# Engine_Room_ADUM_Arduino.net
KiCad netlist of a schematic drawn in EAGLE
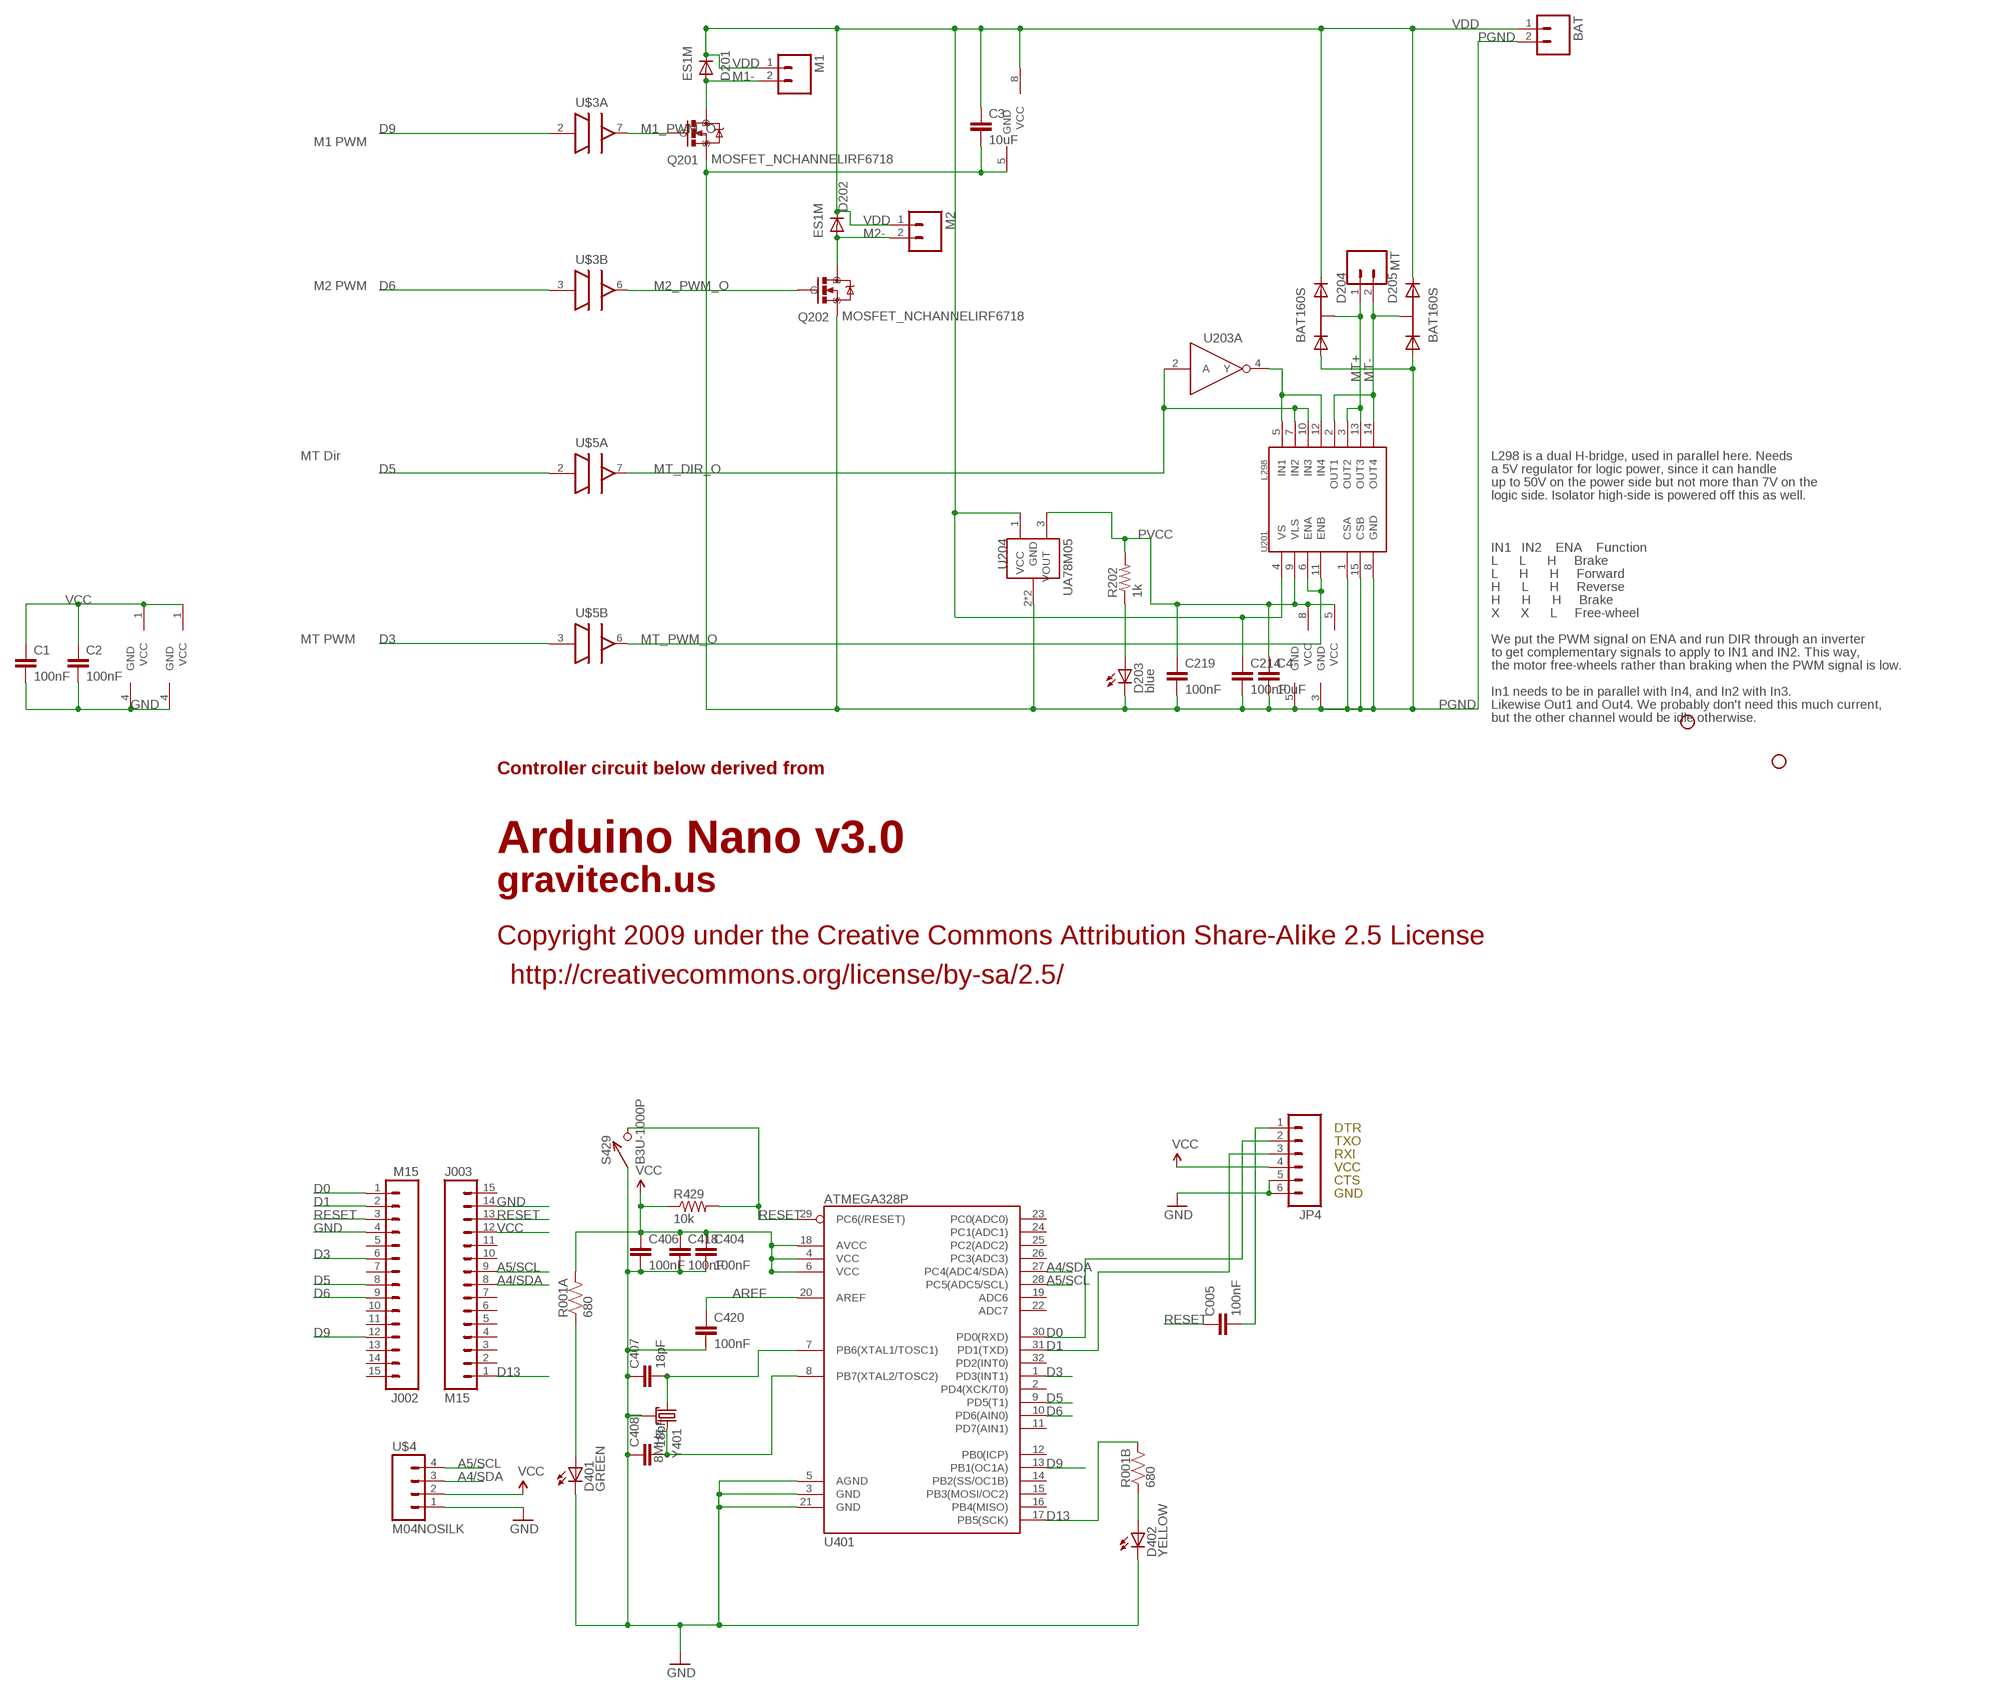
[diagram p0: schematic, sheet 1]

(export (version "E")
  (design (tool "Eeschema 10.0.6"))
  (components
    (comp (ref "BAT")
      (value "M02PTH4")
      (footprint "eagle-import:1X02_XTRA_BIG")
      (libsource (lib "eagle-import") (part "M02PTH4"))
    )
    (comp (ref "C1")
      (value "100nF")
      (footprint "eagle-import:0402-CAP")
      (libsource (lib "eagle-import") (part "CAP0402-CAP"))
    )
    (comp (ref "C2")
      (value "100nF")
      (footprint "eagle-import:0402-CAP")
      (libsource (lib "eagle-import") (part "CAP0402-CAP"))
    )
    (comp (ref "C3")
      (value "10uF")
      (footprint "eagle-import:1206")
      (libsource (lib "eagle-import") (part "SparkFun-Passives_CAP1206"))
    )
    (comp (ref "C4")
      (value "10uF")
      (footprint "eagle-import:1206")
      (libsource (lib "eagle-import") (part "SparkFun-Passives_CAP1206"))
    )
    (comp (ref "C005")
      (value "100nF")
      (footprint "eagle-import:0402-CAP")
      (libsource (lib "eagle-import") (part "CAP0402-CAP"))
    )
    (comp (ref "C214")
      (value "100nF")
      (footprint "eagle-import:1206")
      (libsource (lib "eagle-import") (part "SparkFun-Passives_CAP1206"))
    )
    (comp (ref "C219")
      (value "100nF")
      (footprint "eagle-import:0402-CAP")
      (libsource (lib "eagle-import") (part "CAP0402-CAP"))
    )
    (comp (ref "C404")
      (value "100nF")
      (footprint "eagle-import:0402-CAP")
      (libsource (lib "eagle-import") (part "CAP0402-CAP"))
    )
    (comp (ref "C406")
      (value "100nF")
      (footprint "eagle-import:0402-CAP")
      (libsource (lib "eagle-import") (part "CAP0402-CAP"))
    )
    (comp (ref "C407")
      (value "18pF")
      (footprint "eagle-import:0402-CAP")
      (libsource (lib "eagle-import") (part "CAP0402-CAP"))
    )
    (comp (ref "C408")
      (value "18pF")
      (footprint "eagle-import:0402-CAP")
      (libsource (lib "eagle-import") (part "CAP0402-CAP"))
    )
    (comp (ref "C418")
      (value "100nF")
      (footprint "eagle-import:0402-CAP")
      (libsource (lib "eagle-import") (part "CAP0402-CAP"))
    )
    (comp (ref "C420")
      (value "100nF")
      (footprint "eagle-import:0402-CAP")
      (libsource (lib "eagle-import") (part "CAP0402-CAP"))
    )
    (comp (ref "D201")
      (value "ES1M")
      (footprint "eagle-import:DO-214AC")
      (libsource (lib "eagle-import") (part "DIODE-DO-214AC"))
    )
    (comp (ref "D202")
      (value "ES1M")
      (footprint "eagle-import:DO-214AC")
      (libsource (lib "eagle-import") (part "DIODE-DO-214AC"))
    )
    (comp (ref "D203")
      (value "blue")
      (footprint "eagle-import:LED-0603")
      (libsource (lib "eagle-import") (part "LED0603"))
    )
    (comp (ref "D204")
      (value "BAT160S")
      (footprint "eagle-import:SOT-223")
      (libsource (lib "eagle-import") (part "BAT160S"))
    )
    (comp (ref "D205")
      (value "BAT160S")
      (footprint "eagle-import:SOT-223")
      (libsource (lib "eagle-import") (part "BAT160S"))
    )
    (comp (ref "D401")
      (value "GREEN")
      (footprint "eagle-import:LED-0603")
      (libsource (lib "eagle-import") (part "SparkFun-LED_LED0603"))
    )
    (comp (ref "D402")
      (value "YELLOW")
      (footprint "eagle-import:LED-0603")
      (libsource (lib "eagle-import") (part "SparkFun-LED_LED0603"))
    )
    (comp (ref "J002")
      (value "M15")
      (footprint "eagle-import:1X15")
      (libsource (lib "eagle-import") (part "M15"))
    )
    (comp (ref "J003")
      (value "M15")
      (footprint "eagle-import:1X15")
      (libsource (lib "eagle-import") (part "M15"))
    )
    (comp (ref "JP1")
      (value "STAND-OFF")
      (footprint "eagle-import:STAND-OFF")
      (libsource (lib "eagle-import") (part "STAND-OFF"))
    )
    (comp (ref "JP2")
      (value "STAND-OFF")
      (footprint "eagle-import:STAND-OFF")
      (libsource (lib "eagle-import") (part "STAND-OFF"))
    )
    (comp (ref "JP4")
      (value "M06SIP")
      (footprint "eagle-import:1X06")
      (libsource (lib "eagle-import") (part "M06SIP"))
    )
    (comp (ref "M1")
      (value "M02PTH4")
      (footprint "eagle-import:1X02_XTRA_BIG")
      (libsource (lib "eagle-import") (part "M02PTH4"))
    )
    (comp (ref "M2")
      (value "M02PTH4")
      (footprint "eagle-import:1X02_XTRA_BIG")
      (libsource (lib "eagle-import") (part "M02PTH4"))
    )
    (comp (ref "MT")
      (value "M02PTH")
      (footprint "eagle-import:1X02")
      (libsource (lib "eagle-import") (part "M02PTH"))
    )
    (comp (ref "Q201")
      (value "MOSFET_NCHANNELIRF6718")
      (footprint "eagle-import:DIRECTFET_L6")
      (libsource (lib "eagle-import") (part "MOSFET_NCHANNELIRF6718"))
    )
    (comp (ref "Q202")
      (value "MOSFET_NCHANNELIRF6718")
      (footprint "eagle-import:DIRECTFET_L6")
      (libsource (lib "eagle-import") (part "MOSFET_NCHANNELIRF6718"))
    )
    (comp (ref "R001")
      (value "680")
      (footprint "eagle-import:CRA02")
      (fields (field (name "DIGIKEY") "CRA4S8680CT-ND"))
      (libsource (lib "eagle-import") (part "RP2EXB24V"))
    )
    (comp (ref "R202")
      (value "1k")
      (footprint "eagle-import:0402-RES")
      (libsource (lib "eagle-import") (part "RESISTOR0402-RES"))
    )
    (comp (ref "R429")
      (value "10k")
      (footprint "eagle-import:0402-RES")
      (libsource (lib "eagle-import") (part "SparkFun-Passives_RESISTOR0402-RES"))
    )
    (comp (ref "S429")
      (value "B3U-1000P")
      (footprint "eagle-import:B3U-1000P")
      (libsource (lib "eagle-import") (part "B3U-1000P"))
    )
    (comp (ref "U$3")
      (value "ADUM3221")
      (footprint "eagle-import:SO8N")
      (libsource (lib "eagle-import") (part "ADUM3221"))
    )
    (comp (ref "U$4")
      (value "M04NOSILK")
      (footprint "eagle-import:M04SIP")
      (libsource (lib "eagle-import") (part "M04NOSILK"))
    )
    (comp (ref "U$5")
      (value "ADUM3221")
      (footprint "eagle-import:SO8N")
      (libsource (lib "eagle-import") (part "ADUM3221"))
    )
    (comp (ref "U201")
      (value "L298")
      (footprint "eagle-import:MULTIWATT15")
      (libsource (lib "eagle-import") (part "L298"))
    )
    (comp (ref "U203")
      (value "MC74VHC1G04")
      (footprint "eagle-import:SOT-23-5")
      (libsource (lib "eagle-import") (part "MC74VHC1G04"))
    )
    (comp (ref "U204")
      (value "UA78M05")
      (footprint "eagle-import:SOT-223")
      (libsource (lib "eagle-import") (part "UA78M05"))
    )
    (comp (ref "U401")
      (value "ATMEGA328P")
      (footprint "eagle-import:TQFP32-08")
      (libsource (lib "eagle-import") (part "ATMEGA168"))
    )
    (comp (ref "Y401")
      (value "8MHz")
      (footprint "eagle-import:CRYSTAL_SMD_2MM_2_5MM")
      (libsource (lib "eagle-import") (part "CX2520"))
    )
  )
  (nets
    (net (code "1") (name "/A4{slash}SDA") (class "Default")
      (node (ref "J003") (pin "8") (pinfunction "8_8") (pintype "passive"))
      (node (ref "U$4") (pin "3") (pinfunction "3_3") (pintype "passive"))
      (node (ref "U401") (pin "27") (pinfunction "PC4(ADC4/SDA)_27") (pintype "bidirectional"))
    )
    (net (code "2") (name "/A5{slash}SCL") (class "Default")
      (node (ref "J003") (pin "9") (pinfunction "9_9") (pintype "passive"))
      (node (ref "U$4") (pin "4") (pinfunction "4_4") (pintype "passive"))
      (node (ref "U401") (pin "28") (pinfunction "PC5(ADC5/SCL)_28") (pintype "bidirectional"))
    )
    (net (code "3") (name "/AREF") (class "Default")
      (node (ref "C420") (pin "1") (pinfunction "1_1") (pintype "passive"))
      (node (ref "U401") (pin "20") (pinfunction "AREF_20") (pintype "bidirectional"))
    )
    (net (code "4") (name "/D0") (class "Default")
      (node (ref "J002") (pin "1") (pinfunction "1_1") (pintype "passive"))
      (node (ref "JP4") (pin "2") (pinfunction "2_2") (pintype "passive"))
      (node (ref "U401") (pin "30") (pinfunction "PD0(RXD)_30") (pintype "bidirectional"))
    )
    (net (code "5") (name "/D1") (class "Default")
      (node (ref "J002") (pin "2") (pinfunction "2_2") (pintype "passive"))
      (node (ref "JP4") (pin "3") (pinfunction "3_3") (pintype "passive"))
      (node (ref "U401") (pin "31") (pinfunction "PD1(TXD)_31") (pintype "bidirectional"))
    )
    (net (code "6") (name "/D3") (class "Default")
      (node (ref "J002") (pin "6") (pinfunction "6_6") (pintype "passive"))
      (node (ref "U$5") (pin "3") (pinfunction "IN_3") (pintype "input"))
      (node (ref "U401") (pin "1") (pinfunction "PD3(INT1)_1") (pintype "bidirectional"))
    )
    (net (code "7") (name "/D5") (class "Default")
      (node (ref "J002") (pin "8") (pinfunction "8_8") (pintype "passive"))
      (node (ref "U$5") (pin "2") (pinfunction "IN_2") (pintype "input"))
      (node (ref "U401") (pin "9") (pinfunction "PD5(T1)_9") (pintype "bidirectional"))
    )
    (net (code "8") (name "/D6") (class "Default")
      (node (ref "J002") (pin "9") (pinfunction "9_9") (pintype "passive"))
      (node (ref "U$3") (pin "3") (pinfunction "IN_3") (pintype "input"))
      (node (ref "U401") (pin "10") (pinfunction "PD6(AIN0)_10") (pintype "bidirectional"))
    )
    (net (code "9") (name "/D9") (class "Default")
      (node (ref "J002") (pin "12") (pinfunction "12_12") (pintype "passive"))
      (node (ref "U$3") (pin "2") (pinfunction "IN_2") (pintype "input"))
      (node (ref "U401") (pin "13") (pinfunction "PB1(OC1A)_13") (pintype "bidirectional"))
    )
    (net (code "10") (name "/D13") (class "Default")
      (node (ref "J003") (pin "1") (pinfunction "1_1") (pintype "passive"))
      (node (ref "R001") (pin "3") (pinfunction "2_3") (pintype "passive"))
      (node (ref "U401") (pin "17") (pinfunction "PB5(SCK)_17") (pintype "bidirectional"))
    )
    (net (code "11") (name "/M1-") (class "Default")
      (node (ref "D201") (pin "A") (pinfunction "A_A") (pintype "passive"))
      (node (ref "M1") (pin "2") (pinfunction "2_2") (pintype "passive"))
      (node (ref "Q201") (pin "D1") (pinfunction "D_D1") (pintype "passive"))
      (node (ref "Q201") (pin "D2") (pinfunction "D_D2") (pintype "passive"))
    )
    (net (code "12") (name "/M1_PWM_O") (class "Default")
      (node (ref "Q201") (pin "G") (pinfunction "G_G") (pintype "passive"))
      (node (ref "U$3") (pin "7") (pinfunction "OUT_7") (pintype "bidirectional"))
    )
    (net (code "13") (name "/M2-") (class "Default")
      (node (ref "D202") (pin "A") (pinfunction "A_A") (pintype "passive"))
      (node (ref "M2") (pin "2") (pinfunction "2_2") (pintype "passive"))
      (node (ref "Q202") (pin "D1") (pinfunction "D_D1") (pintype "passive"))
      (node (ref "Q202") (pin "D2") (pinfunction "D_D2") (pintype "passive"))
    )
    (net (code "14") (name "/M2_PWM_O") (class "Default")
      (node (ref "Q202") (pin "G") (pinfunction "G_G") (pintype "passive"))
      (node (ref "U$3") (pin "6") (pinfunction "OUT_6") (pintype "bidirectional"))
    )
    (net (code "15") (name "/MT+") (class "Default")
      (node (ref "D204") (pin "4") (pinfunction "K1A2_4") (pintype "passive"))
      (node (ref "MT") (pin "1") (pinfunction "1_1") (pintype "passive"))
      (node (ref "U201") (pin "13") (pinfunction "OUT3_13") (pintype "bidirectional"))
      (node (ref "U201") (pin "3") (pinfunction "OUT2_3") (pintype "bidirectional"))
    )
    (net (code "16") (name "/MT-") (class "Default")
      (node (ref "D205") (pin "4") (pinfunction "K1A2_4") (pintype "passive"))
      (node (ref "MT") (pin "2") (pinfunction "2_2") (pintype "passive"))
      (node (ref "U201") (pin "14") (pinfunction "OUT4_14") (pintype "bidirectional"))
      (node (ref "U201") (pin "2") (pinfunction "OUT1_2") (pintype "bidirectional"))
    )
    (net (code "17") (name "/MT_DIR_O") (class "Default")
      (node (ref "U$5") (pin "7") (pinfunction "OUT_7") (pintype "bidirectional"))
      (node (ref "U201") (pin "10") (pinfunction "IN3_10") (pintype "bidirectional"))
      (node (ref "U201") (pin "7") (pinfunction "IN2_7") (pintype "bidirectional"))
      (node (ref "U203") (pin "2") (pinfunction "A_2") (pintype "input"))
    )
    (net (code "18") (name "/MT_PWM_O") (class "Default")
      (node (ref "U$5") (pin "6") (pinfunction "OUT_6") (pintype "bidirectional"))
      (node (ref "U201") (pin "11") (pinfunction "ENB_11") (pintype "bidirectional"))
      (node (ref "U201") (pin "6") (pinfunction "ENA_6") (pintype "bidirectional"))
    )
    (net (code "19") (name "/PGND") (class "Default")
      (node (ref "BAT") (pin "2") (pinfunction "2_2") (pintype "passive"))
      (node (ref "C214") (pin "2") (pinfunction "2_2") (pintype "passive"))
      (node (ref "C219") (pin "2") (pinfunction "2_2") (pintype "passive"))
      (node (ref "C3") (pin "2") (pinfunction "2_2") (pintype "passive"))
      (node (ref "C4") (pin "2") (pinfunction "2_2") (pintype "passive"))
      (node (ref "D203") (pin "C") (pinfunction "C_C") (pintype "passive"))
      (node (ref "D204") (pin "1") (pinfunction "A1_1") (pintype "passive"))
      (node (ref "D205") (pin "1") (pinfunction "A1_1") (pintype "passive"))
      (node (ref "Q201") (pin "S") (pinfunction "S_S") (pintype "passive"))
      (node (ref "Q202") (pin "S") (pinfunction "S_S") (pintype "passive"))
      (node (ref "U$3") (pin "5") (pinfunction "GND_5") (pintype "bidirectional"))
      (node (ref "U$5") (pin "5") (pinfunction "GND_5") (pintype "bidirectional"))
      (node (ref "U201") (pin "1") (pinfunction "CSA_1") (pintype "bidirectional"))
      (node (ref "U201") (pin "15") (pinfunction "CSB_15") (pintype "bidirectional"))
      (node (ref "U201") (pin "8") (pinfunction "GND_8") (pintype "bidirectional"))
      (node (ref "U203") (pin "3") (pinfunction "GND_3") (pintype "bidirectional"))
      (node (ref "U204") (pin "2") (pinfunction "GND_2") (pintype "bidirectional"))
      (node (ref "U204") (pin "4") (pinfunction "GND_4") (pintype "bidirectional"))
    )
    (net (code "20") (name "/PVCC") (class "Default")
      (node (ref "C219") (pin "1") (pinfunction "1_1") (pintype "passive"))
      (node (ref "C4") (pin "1") (pinfunction "1_1") (pintype "passive"))
      (node (ref "R202") (pin "2") (pinfunction "2_2") (pintype "passive"))
      (node (ref "U$5") (pin "8") (pinfunction "VCC_8") (pintype "bidirectional"))
      (node (ref "U201") (pin "9") (pinfunction "VLS_9") (pintype "bidirectional"))
      (node (ref "U203") (pin "5") (pinfunction "VCC_5") (pintype "bidirectional"))
      (node (ref "U204") (pin "3") (pinfunction "VOUT_3") (pintype "bidirectional"))
    )
    (net (code "21") (name "/RESET") (class "Default")
      (node (ref "C005") (pin "1") (pinfunction "1_1") (pintype "passive"))
      (node (ref "J002") (pin "3") (pinfunction "3_3") (pintype "passive"))
      (node (ref "J003") (pin "13") (pinfunction "13_13") (pintype "passive"))
      (node (ref "R429") (pin "2") (pinfunction "2_2") (pintype "passive"))
      (node (ref "S429") (pin "P$2") (pinfunction "2_P$2") (pintype "bidirectional"))
      (node (ref "U401") (pin "29") (pinfunction "PC6(/RESET)_29") (pintype "bidirectional"))
    )
    (net (code "22") (name "/VDD") (class "Default")
      (node (ref "BAT") (pin "1") (pinfunction "1_1") (pintype "passive"))
      (node (ref "C214") (pin "1") (pinfunction "1_1") (pintype "passive"))
      (node (ref "C3") (pin "1") (pinfunction "1_1") (pintype "passive"))
      (node (ref "D201") (pin "C") (pinfunction "C_C") (pintype "passive"))
      (node (ref "D202") (pin "C") (pinfunction "C_C") (pintype "passive"))
      (node (ref "D204") (pin "3") (pinfunction "K2_3") (pintype "passive"))
      (node (ref "D205") (pin "3") (pinfunction "K2_3") (pintype "passive"))
      (node (ref "M1") (pin "1") (pinfunction "1_1") (pintype "passive"))
      (node (ref "M2") (pin "1") (pinfunction "1_1") (pintype "passive"))
      (node (ref "U$3") (pin "8") (pinfunction "VCC_8") (pintype "bidirectional"))
      (node (ref "U201") (pin "4") (pinfunction "VS_4") (pintype "bidirectional"))
      (node (ref "U204") (pin "1") (pinfunction "VCC_1") (pintype "bidirectional"))
    )
    (net (code "23") (name "GND") (class "Default")
      (node (ref "C1") (pin "2") (pinfunction "2_2") (pintype "passive"))
      (node (ref "C2") (pin "2") (pinfunction "2_2") (pintype "passive"))
      (node (ref "C404") (pin "2") (pinfunction "2_2") (pintype "passive"))
      (node (ref "C406") (pin "2") (pinfunction "2_2") (pintype "passive"))
      (node (ref "C407") (pin "1") (pinfunction "1_1") (pintype "passive"))
      (node (ref "C408") (pin "1") (pinfunction "1_1") (pintype "passive"))
      (node (ref "C418") (pin "2") (pinfunction "2_2") (pintype "passive"))
      (node (ref "C420") (pin "2") (pinfunction "2_2") (pintype "passive"))
      (node (ref "D401") (pin "C") (pinfunction "C_C") (pintype "passive"))
      (node (ref "D402") (pin "C") (pinfunction "C_C") (pintype "passive"))
      (node (ref "J002") (pin "4") (pinfunction "4_4") (pintype "passive"))
      (node (ref "J003") (pin "14") (pinfunction "14_14") (pintype "passive"))
      (node (ref "JP4") (pin "5") (pinfunction "5_5") (pintype "passive"))
      (node (ref "JP4") (pin "6") (pinfunction "6_6") (pintype "passive"))
      (node (ref "S429") (pin "P$1") (pinfunction "1_P$1") (pintype "bidirectional"))
      (node (ref "U$3") (pin "4") (pinfunction "GND_4") (pintype "bidirectional"))
      (node (ref "U$4") (pin "1") (pinfunction "1_1") (pintype "passive"))
      (node (ref "U$5") (pin "4") (pinfunction "GND_4") (pintype "bidirectional"))
      (node (ref "U401") (pin "21") (pinfunction "GND_21") (pintype "bidirectional"))
      (node (ref "U401") (pin "3") (pinfunction "GND_3") (pintype "bidirectional"))
      (node (ref "U401") (pin "5") (pinfunction "AGND_5") (pintype "bidirectional"))
      (node (ref "Y401") (pin "2") (pinfunction "GND_2") (pintype "passive"))
      (node (ref "Y401") (pin "4") (pinfunction "GND_4") (pintype "passive"))
    )
    (net (code "24") (name "Net-(C005-Pad2)") (class "Default")
      (node (ref "C005") (pin "2") (pinfunction "2_2") (pintype "passive"))
      (node (ref "JP4") (pin "1") (pinfunction "1_1") (pintype "passive"))
    )
    (net (code "25") (name "Net-(D203-PadA)") (class "Default")
      (node (ref "D203") (pin "A") (pinfunction "A_A") (pintype "passive"))
      (node (ref "R202") (pin "1") (pinfunction "1_1") (pintype "passive"))
    )
    (net (code "26") (name "Net-(D401-PadA)") (class "Default")
      (node (ref "D401") (pin "A") (pinfunction "A_A") (pintype "passive"))
      (node (ref "R001") (pin "1") (pinfunction "1_1") (pintype "passive"))
    )
    (net (code "27") (name "Net-(R001B-1)") (class "Default")
      (node (ref "D402") (pin "A") (pinfunction "A_A") (pintype "passive"))
      (node (ref "R001") (pin "2") (pinfunction "1_2") (pintype "passive"))
    )
    (net (code "28") (name "Net-(U201-IN1)") (class "Default")
      (node (ref "U201") (pin "12") (pinfunction "IN4_12") (pintype "bidirectional"))
      (node (ref "U201") (pin "5") (pinfunction "IN1_5") (pintype "bidirectional"))
      (node (ref "U203") (pin "4") (pinfunction "Y_4") (pintype "output"))
    )
    (net (code "29") (name "Net-(U401-PB6(XTAL1{slash}TOSC1))") (class "Default")
      (node (ref "C407") (pin "2") (pinfunction "2_2") (pintype "passive"))
      (node (ref "U401") (pin "7") (pinfunction "PB6(XTAL1/TOSC1)_7") (pintype "bidirectional"))
      (node (ref "Y401") (pin "1") (pinfunction "1_1") (pintype "passive"))
    )
    (net (code "30") (name "Net-(U401-PB7(XTAL2{slash}TOSC2))") (class "Default")
      (node (ref "C408") (pin "2") (pinfunction "2_2") (pintype "passive"))
      (node (ref "U401") (pin "8") (pinfunction "PB7(XTAL2/TOSC2)_8") (pintype "bidirectional"))
      (node (ref "Y401") (pin "3") (pinfunction "2_3") (pintype "passive"))
    )
    (net (code "31") (name "VCC") (class "Default")
      (node (ref "C1") (pin "1") (pinfunction "1_1") (pintype "passive"))
      (node (ref "C2") (pin "1") (pinfunction "1_1") (pintype "passive"))
      (node (ref "C404") (pin "1") (pinfunction "1_1") (pintype "passive"))
      (node (ref "C406") (pin "1") (pinfunction "1_1") (pintype "passive"))
      (node (ref "C418") (pin "1") (pinfunction "1_1") (pintype "passive"))
      (node (ref "J003") (pin "12") (pinfunction "12_12") (pintype "passive"))
      (node (ref "JP4") (pin "4") (pinfunction "4_4") (pintype "passive"))
      (node (ref "R001") (pin "4") (pinfunction "2_4") (pintype "passive"))
      (node (ref "R429") (pin "1") (pinfunction "1_1") (pintype "passive"))
      (node (ref "U$3") (pin "1") (pinfunction "VCC_1") (pintype "bidirectional"))
      (node (ref "U$4") (pin "2") (pinfunction "2_2") (pintype "passive"))
      (node (ref "U$5") (pin "1") (pinfunction "VCC_1") (pintype "bidirectional"))
      (node (ref "U401") (pin "18") (pinfunction "AVCC_18") (pintype "bidirectional"))
      (node (ref "U401") (pin "4") (pinfunction "VCC_4") (pintype "bidirectional"))
      (node (ref "U401") (pin "6") (pinfunction "VCC_6") (pintype "bidirectional"))
    )
    (net (code "32") (name "unconnected-(J002-Pad5)") (class "Default")
      (node (ref "J002") (pin "5") (pinfunction "5_5") (pintype "passive"))
    )
    (net (code "33") (name "unconnected-(J002-Pad7)") (class "Default")
      (node (ref "J002") (pin "7") (pinfunction "7_7") (pintype "passive"))
    )
    (net (code "34") (name "unconnected-(J002-Pad10)") (class "Default")
      (node (ref "J002") (pin "10") (pinfunction "10_10") (pintype "passive"))
    )
    (net (code "35") (name "unconnected-(J002-Pad11)") (class "Default")
      (node (ref "J002") (pin "11") (pinfunction "11_11") (pintype "passive"))
    )
    (net (code "36") (name "unconnected-(J002-Pad13)") (class "Default")
      (node (ref "J002") (pin "13") (pinfunction "13_13") (pintype "passive"))
    )
    (net (code "37") (name "unconnected-(J002-Pad14)") (class "Default")
      (node (ref "J002") (pin "14") (pinfunction "14_14") (pintype "passive"))
    )
    (net (code "38") (name "unconnected-(J002-Pad15)") (class "Default")
      (node (ref "J002") (pin "15") (pinfunction "15_15") (pintype "passive"))
    )
    (net (code "39") (name "unconnected-(J003-Pad2)") (class "Default")
      (node (ref "J003") (pin "2") (pinfunction "2_2") (pintype "passive"))
    )
    (net (code "40") (name "unconnected-(J003-Pad3)") (class "Default")
      (node (ref "J003") (pin "3") (pinfunction "3_3") (pintype "passive"))
    )
    (net (code "41") (name "unconnected-(J003-Pad4)") (class "Default")
      (node (ref "J003") (pin "4") (pinfunction "4_4") (pintype "passive"))
    )
    (net (code "42") (name "unconnected-(J003-Pad5)") (class "Default")
      (node (ref "J003") (pin "5") (pinfunction "5_5") (pintype "passive"))
    )
    (net (code "43") (name "unconnected-(J003-Pad6)") (class "Default")
      (node (ref "J003") (pin "6") (pinfunction "6_6") (pintype "passive"))
    )
    (net (code "44") (name "unconnected-(J003-Pad7)") (class "Default")
      (node (ref "J003") (pin "7") (pinfunction "7_7") (pintype "passive"))
    )
    (net (code "45") (name "unconnected-(J003-Pad10)") (class "Default")
      (node (ref "J003") (pin "10") (pinfunction "10_10") (pintype "passive"))
    )
    (net (code "46") (name "unconnected-(J003-Pad11)") (class "Default")
      (node (ref "J003") (pin "11") (pinfunction "11_11") (pintype "passive"))
    )
    (net (code "47") (name "unconnected-(J003-Pad15)") (class "Default")
      (node (ref "J003") (pin "15") (pinfunction "15_15") (pintype "passive"))
    )
    (net (code "48") (name "unconnected-(U401-ADC6-Pad19)") (class "Default")
      (node (ref "U401") (pin "19") (pinfunction "ADC6_19") (pintype "bidirectional"))
    )
    (net (code "49") (name "unconnected-(U401-ADC7-Pad22)") (class "Default")
      (node (ref "U401") (pin "22") (pinfunction "ADC7_22") (pintype "bidirectional"))
    )
    (net (code "50") (name "unconnected-(U401-PB0(ICP)-Pad12)") (class "Default")
      (node (ref "U401") (pin "12") (pinfunction "PB0(ICP)_12") (pintype "bidirectional"))
    )
    (net (code "51") (name "unconnected-(U401-PB2(SS{slash}OC1B)-Pad14)") (class "Default")
      (node (ref "U401") (pin "14") (pinfunction "PB2(SS/OC1B)_14") (pintype "bidirectional"))
    )
    (net (code "52") (name "unconnected-(U401-PB3(MOSI{slash}OC2)-Pad15)") (class "Default")
      (node (ref "U401") (pin "15") (pinfunction "PB3(MOSI/OC2)_15") (pintype "bidirectional"))
    )
    (net (code "53") (name "unconnected-(U401-PB4(MISO)-Pad16)") (class "Default")
      (node (ref "U401") (pin "16") (pinfunction "PB4(MISO)_16") (pintype "bidirectional"))
    )
    (net (code "54") (name "unconnected-(U401-PC0(ADC0)-Pad23)") (class "Default")
      (node (ref "U401") (pin "23") (pinfunction "PC0(ADC0)_23") (pintype "bidirectional"))
    )
    (net (code "55") (name "unconnected-(U401-PC1(ADC1)-Pad24)") (class "Default")
      (node (ref "U401") (pin "24") (pinfunction "PC1(ADC1)_24") (pintype "bidirectional"))
    )
    (net (code "56") (name "unconnected-(U401-PC2(ADC2)-Pad25)") (class "Default")
      (node (ref "U401") (pin "25") (pinfunction "PC2(ADC2)_25") (pintype "bidirectional"))
    )
    (net (code "57") (name "unconnected-(U401-PC3(ADC3)-Pad26)") (class "Default")
      (node (ref "U401") (pin "26") (pinfunction "PC3(ADC3)_26") (pintype "bidirectional"))
    )
    (net (code "58") (name "unconnected-(U401-PD2(INT0)-Pad32)") (class "Default")
      (node (ref "U401") (pin "32") (pinfunction "PD2(INT0)_32") (pintype "bidirectional"))
    )
    (net (code "59") (name "unconnected-(U401-PD4(XCK{slash}T0)-Pad2)") (class "Default")
      (node (ref "U401") (pin "2") (pinfunction "PD4(XCK/T0)_2") (pintype "bidirectional"))
    )
    (net (code "60") (name "unconnected-(U401-PD7(AIN1)-Pad11)") (class "Default")
      (node (ref "U401") (pin "11") (pinfunction "PD7(AIN1)_11") (pintype "bidirectional"))
    )
  )
)
